# logger100.net
KiCad netlist of a schematic drawn in EAGLE
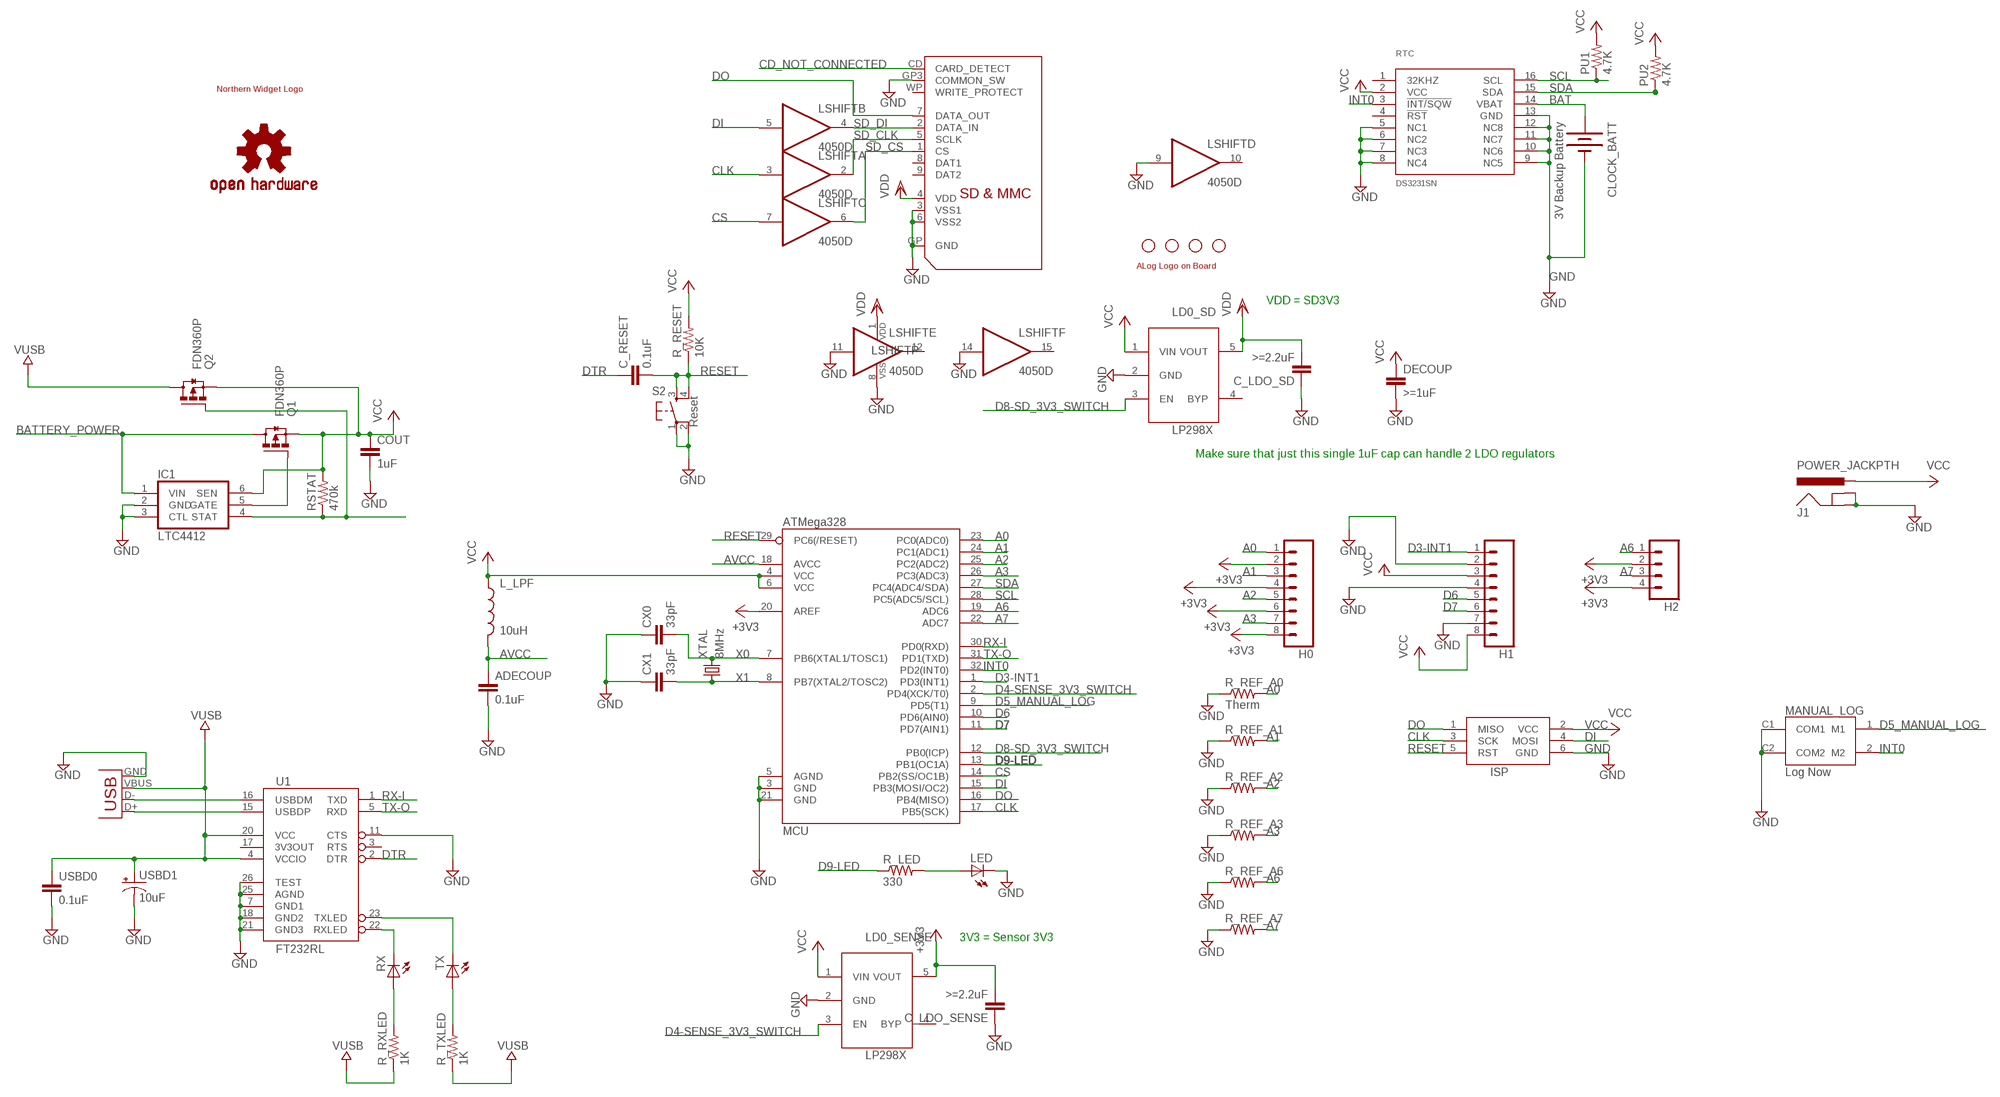
[diagram p0: schematic, sheet 1]

(export (version "E")
  (design (tool "Eeschema 10.0.6"))
  (components
    (comp (ref "ADECOUP")
      (value "0.1uF")
      (footprint "eagle-import:C0603")
      (libsource (lib "eagle-import") (part "resistor_C-EUC0603"))
    )
    (comp (ref "CLOCK_BATT")
      (value "3V Backup Battery")
      (footprint "eagle-import:BATTCON_12MM_PTH")
      (libsource (lib "eagle-import") (part "BATTERY12PTH"))
    )
    (comp (ref "COUT")
      (value "1uF")
      (footprint "eagle-import:C0603-ROUND")
      (libsource (lib "eagle-import") (part "C-EUC0603"))
    )
    (comp (ref "CX0")
      (value "33pF")
      (footprint "eagle-import:C0603")
      (libsource (lib "eagle-import") (part "resistor_C-EUC0603"))
    )
    (comp (ref "CX1")
      (value "33pF")
      (footprint "eagle-import:C0603")
      (libsource (lib "eagle-import") (part "resistor_C-EUC0603"))
    )
    (comp (ref "C_LDO_SD")
      (value ">=2.2uF")
      (footprint "eagle-import:C0603")
      (libsource (lib "eagle-import") (part "resistor_C-EUC0603"))
    )
    (comp (ref "C_LDO_SENSE")
      (value ">=2.2uF")
      (footprint "eagle-import:C0603")
      (libsource (lib "eagle-import") (part "resistor_C-EUC0603"))
    )
    (comp (ref "C_RESET")
      (value "0.1uF")
      (footprint "eagle-import:C0603")
      (libsource (lib "eagle-import") (part "resistor_C-EUC0603"))
    )
    (comp (ref "DECOUP")
      (value ">=1uF")
      (footprint "eagle-import:C0603")
      (libsource (lib "eagle-import") (part "resistor_C-EUC0603"))
    )
    (comp (ref "H0")
      (value "M083.5MM-8")
      (footprint "eagle-import:SCREWTERMINAL-3.5MM-8")
      (libsource (lib "eagle-import") (part "M083.5MM-8"))
    )
    (comp (ref "H1")
      (value "M083.5MM-8")
      (footprint "eagle-import:SCREWTERMINAL-3.5MM-8")
      (libsource (lib "eagle-import") (part "M083.5MM-8"))
    )
    (comp (ref "H2")
      (value "M04SCREW")
      (footprint "eagle-import:SCREWTERMINAL-3.5MM-4")
      (libsource (lib "eagle-import") (part "M04SCREW"))
    )
    (comp (ref "IC1")
      (value "LTC4412")
      (footprint "eagle-import:TSOT23-6")
      (libsource (lib "eagle-import") (part "LTC4412S6E"))
    )
    (comp (ref "ISP")
      (value "AVRISP-6")
      (footprint "eagle-import:AVRISP")
      (libsource (lib "eagle-import") (part "AVRISP-6"))
    )
    (comp (ref "J1")
      (value "POWER_JACKPTH")
      (footprint "eagle-import:POWER_JACK_PTH")
      (libsource (lib "eagle-import") (part "POWER_JACKPTH"))
    )
    (comp (ref "JP1")
      (value "STAND-OFF")
      (footprint "eagle-import:STAND-OFF")
      (libsource (lib "eagle-import") (part "STAND-OFF"))
    )
    (comp (ref "JP2")
      (value "STAND-OFF")
      (footprint "eagle-import:STAND-OFF")
      (libsource (lib "eagle-import") (part "STAND-OFF"))
    )
    (comp (ref "JP3")
      (value "STAND-OFF")
      (footprint "eagle-import:STAND-OFF")
      (libsource (lib "eagle-import") (part "STAND-OFF"))
    )
    (comp (ref "JP4")
      (value "STAND-OFF")
      (footprint "eagle-import:STAND-OFF")
      (libsource (lib "eagle-import") (part "STAND-OFF"))
    )
    (comp (ref "JP5")
      (value "USB-B")
      (footprint "eagle-import:USB-B-PTH")
      (libsource (lib "eagle-import") (part "USBPTH"))
    )
    (comp (ref "LD0_SD")
      (value "LP2985")
      (footprint "eagle-import:SOT23-5L")
      (libsource (lib "eagle-import") (part "LP298XS"))
    )
    (comp (ref "LD0_SENSE")
      (value "LP2985")
      (footprint "eagle-import:SOT23-5L")
      (libsource (lib "eagle-import") (part "LP298XS"))
    )
    (comp (ref "LED")
      (value "LED3MM")
      (footprint "eagle-import:LED3MM")
      (libsource (lib "eagle-import") (part "LED3MM"))
    )
    (comp (ref "LOGO1")
      (value "OSHW-LOGOM")
      (footprint "eagle-import:OSHW-LOGO-M")
      (libsource (lib "eagle-import") (part "OSHW-LOGOM"))
    )
    (comp (ref "LSHIFT")
      (value "4050D")
      (footprint "eagle-import:SO16")
      (libsource (lib "eagle-import") (part "4050D"))
    )
    (comp (ref "L_LPF")
      (value "10uH")
      (footprint "eagle-import:0805")
      (libsource (lib "eagle-import") (part "INDUCTOR0805"))
    )
    (comp (ref "MANUAL_LOG")
      (value "Log Now")
      (footprint "eagle-import:TL_BUTTON")
      (libsource (lib "eagle-import") (part "TL3350'TL3350'"))
    )
    (comp (ref "MCU")
      (value "ATMega328")
      (footprint "eagle-import:TQFP32-08")
      (libsource (lib "eagle-import") (part "ATMEGA168"))
    )
    (comp (ref "PU1")
      (value "4.7K")
      (footprint "eagle-import:R0603")
      (libsource (lib "eagle-import") (part "R-US_R0603"))
    )
    (comp (ref "PU2")
      (value "4.7K")
      (footprint "eagle-import:R0603")
      (libsource (lib "eagle-import") (part "R-US_R0603"))
    )
    (comp (ref "Q1")
      (value "FDN360P")
      (footprint "eagle-import:SUPER-SOT3")
      (libsource (lib "eagle-import") (part "FDN360P"))
    )
    (comp (ref "Q2")
      (value "FDN360P")
      (footprint "eagle-import:SUPER-SOT3")
      (libsource (lib "eagle-import") (part "FDN360P"))
    )
    (comp (ref "RSTAT")
      (value "470k")
      (footprint "eagle-import:R0603")
      (libsource (lib "eagle-import") (part "R-US_R0603"))
    )
    (comp (ref "RTC")
      (value "DS3231SN")
      (footprint "eagle-import:SO16W")
      (libsource (lib "eagle-import") (part "DS3231SN"))
    )
    (comp (ref "RX")
      (value "LED0603")
      (footprint "eagle-import:LED-0603")
      (libsource (lib "eagle-import") (part "SparkFun-LED_LED0603"))
    )
    (comp (ref "R_LED")
      (value "330")
      (footprint "eagle-import:R0603")
      (libsource (lib "eagle-import") (part "R-US_R0603"))
    )
    (comp (ref "R_REF_A0")
      (value "Therm")
      (footprint "eagle-import:0207_10")
      (libsource (lib "eagle-import") (part "resistor_R-US_0207/10"))
    )
    (comp (ref "R_REF_A1")
      (value "R-US_0207/10")
      (footprint "eagle-import:0207_10")
      (libsource (lib "eagle-import") (part "resistor_R-US_0207/10"))
    )
    (comp (ref "R_REF_A2")
      (value "R-US_0207/10")
      (footprint "eagle-import:0207_10")
      (libsource (lib "eagle-import") (part "resistor_R-US_0207/10"))
    )
    (comp (ref "R_REF_A3")
      (value "R-US_0207/10")
      (footprint "eagle-import:0207_10")
      (libsource (lib "eagle-import") (part "resistor_R-US_0207/10"))
    )
    (comp (ref "R_REF_A6")
      (value "R-US_0207/10")
      (footprint "eagle-import:0207_10")
      (libsource (lib "eagle-import") (part "resistor_R-US_0207/10"))
    )
    (comp (ref "R_REF_A7")
      (value "R-US_0207/10")
      (footprint "eagle-import:0207_10")
      (libsource (lib "eagle-import") (part "resistor_R-US_0207/10"))
    )
    (comp (ref "R_RESET")
      (value "10K")
      (footprint "eagle-import:R0603")
      (libsource (lib "eagle-import") (part "R-US_R0603"))
    )
    (comp (ref "R_RXLED")
      (value "1K")
      (footprint "eagle-import:R0603")
      (libsource (lib "eagle-import") (part "R-US_R0603"))
    )
    (comp (ref "R_TXLED")
      (value "1K")
      (footprint "eagle-import:R0603")
      (libsource (lib "eagle-import") (part "R-US_R0603"))
    )
    (comp (ref "S2")
      (value "Reset")
      (footprint "eagle-import:TACTILE_SWITCH_SMD")
      (libsource (lib "eagle-import") (part "TAC_SWITCHSND"))
    )
    (comp (ref "SD")
      (value "SDMMC06132")
      (footprint "eagle-import:06132")
      (libsource (lib "eagle-import") (part "SDMMC06132"))
    )
    (comp (ref "TX")
      (value "LED0603")
      (footprint "eagle-import:LED-0603")
      (libsource (lib "eagle-import") (part "SparkFun-LED_LED0603"))
    )
    (comp (ref "U$1")
      (value "NWLOGO")
      (footprint "eagle-import:NWLOGO")
      (libsource (lib "eagle-import") (part "NWLOGO"))
    )
    (comp (ref "U$2")
      (value "ALOG_LOGO_V1_5.5MM")
      (footprint "eagle-import:ALOG_LOGO_V1_SMALL")
      (libsource (lib "eagle-import") (part "ALOG_LOGO_V1_5.5MM"))
    )
    (comp (ref "U1")
      (value "FT232RL")
      (footprint "eagle-import:SSOP28DB")
      (libsource (lib "eagle-import") (part "FT232RL-BASICSSOP"))
    )
    (comp (ref "USBD0")
      (value "0.1uF")
      (footprint "eagle-import:C0603")
      (libsource (lib "eagle-import") (part "resistor_C-EUC0603"))
    )
    (comp (ref "USBD1")
      (value "10uF")
      (footprint "eagle-import:EIA3216")
      (libsource (lib "eagle-import") (part "CAP_POL1206"))
    )
    (comp (ref "XTAL")
      (value "8MHz")
      (footprint "eagle-import:HC49U-V")
      (libsource (lib "eagle-import") (part "CRYSTALHC49UV"))
    )
  )
  (nets
    (net (code "1") (name "+3V3") (class "Default")
      (node (ref "C_LDO_SENSE") (pin "2") (pinfunction "2_2") (pintype "passive"))
      (node (ref "H0") (pin "2") (pinfunction "2_2") (pintype "passive"))
      (node (ref "H0") (pin "4") (pinfunction "4_4") (pintype "passive"))
      (node (ref "H0") (pin "6") (pinfunction "6_6") (pintype "passive"))
      (node (ref "H0") (pin "8") (pinfunction "8_8") (pintype "passive"))
      (node (ref "H2") (pin "2") (pinfunction "2_2") (pintype "passive"))
      (node (ref "H2") (pin "4") (pinfunction "4_4") (pintype "passive"))
      (node (ref "LD0_SENSE") (pin "5") (pinfunction "VOUT_5") (pintype "bidirectional"))
      (node (ref "MCU") (pin "20") (pinfunction "AREF_20") (pintype "bidirectional"))
    )
    (net (code "2") (name "/A0") (class "Default")
      (node (ref "H0") (pin "1") (pinfunction "1_1") (pintype "passive"))
      (node (ref "MCU") (pin "23") (pinfunction "PC0(ADC0)_23") (pintype "bidirectional"))
      (node (ref "R_REF_A0") (pin "2") (pinfunction "2_2") (pintype "passive"))
    )
    (net (code "3") (name "/A1") (class "Default")
      (node (ref "H0") (pin "3") (pinfunction "3_3") (pintype "passive"))
      (node (ref "MCU") (pin "24") (pinfunction "PC1(ADC1)_24") (pintype "bidirectional"))
      (node (ref "R_REF_A1") (pin "2") (pinfunction "2_2") (pintype "passive"))
    )
    (net (code "4") (name "/A2") (class "Default")
      (node (ref "H0") (pin "5") (pinfunction "5_5") (pintype "passive"))
      (node (ref "MCU") (pin "25") (pinfunction "PC2(ADC2)_25") (pintype "bidirectional"))
      (node (ref "R_REF_A2") (pin "2") (pinfunction "2_2") (pintype "passive"))
    )
    (net (code "5") (name "/A3") (class "Default")
      (node (ref "H0") (pin "7") (pinfunction "7_7") (pintype "passive"))
      (node (ref "MCU") (pin "26") (pinfunction "PC3(ADC3)_26") (pintype "bidirectional"))
      (node (ref "R_REF_A3") (pin "2") (pinfunction "2_2") (pintype "passive"))
    )
    (net (code "6") (name "/A6") (class "Default")
      (node (ref "H2") (pin "1") (pinfunction "1_1") (pintype "passive"))
      (node (ref "MCU") (pin "19") (pinfunction "ADC6_19") (pintype "bidirectional"))
      (node (ref "R_REF_A6") (pin "2") (pinfunction "2_2") (pintype "passive"))
    )
    (net (code "7") (name "/A7") (class "Default")
      (node (ref "H2") (pin "3") (pinfunction "3_3") (pintype "passive"))
      (node (ref "MCU") (pin "22") (pinfunction "ADC7_22") (pintype "bidirectional"))
      (node (ref "R_REF_A7") (pin "2") (pinfunction "2_2") (pintype "passive"))
    )
    (net (code "8") (name "/AVCC") (class "Default")
      (node (ref "ADECOUP") (pin "1") (pinfunction "1_1") (pintype "passive"))
      (node (ref "L_LPF") (pin "2") (pinfunction "2_2") (pintype "passive"))
      (node (ref "MCU") (pin "18") (pinfunction "AVCC_18") (pintype "bidirectional"))
    )
    (net (code "9") (name "/BAT") (class "Default")
      (node (ref "CLOCK_BATT") (pin "VCC@1") (pinfunction "+_VCC@1") (pintype "power_in"))
      (node (ref "RTC") (pin "14") (pinfunction "VBAT_14") (pintype "bidirectional"))
    )
    (net (code "10") (name "/BATTERY_POWER") (class "Default")
      (node (ref "IC1") (pin "1") (pinfunction "VIN_1") (pintype "input"))
      (node (ref "Q1") (pin "3") (pinfunction "D_3") (pintype "passive"))
    )
    (net (code "11") (name "/CD_NOT_CONNECTED") (class "Default")
      (node (ref "SD") (pin "CD") (pinfunction "CARD_DETECT_CD") (pintype "passive"))
    )
    (net (code "12") (name "/CLK") (class "Default")
      (node (ref "ISP") (pin "3") (pinfunction "SCK_3") (pintype "output"))
      (node (ref "LSHIFT") (pin "3") (pinfunction "I_3") (pintype "input"))
      (node (ref "MCU") (pin "17") (pinfunction "PB5(SCK)_17") (pintype "bidirectional"))
    )
    (net (code "13") (name "/CS") (class "Default")
      (node (ref "LSHIFT") (pin "7") (pinfunction "I_7") (pintype "input"))
      (node (ref "MCU") (pin "14") (pinfunction "PB2(SS/OC1B)_14") (pintype "bidirectional"))
    )
    (net (code "14") (name "/D3-INT1") (class "Default")
      (node (ref "H1") (pin "1") (pinfunction "1_1") (pintype "passive"))
      (node (ref "MCU") (pin "1") (pinfunction "PD3(INT1)_1") (pintype "bidirectional"))
    )
    (net (code "15") (name "/D4-SENSE_3V3_SWITCH") (class "Default")
      (node (ref "LD0_SENSE") (pin "3") (pinfunction "EN_3") (pintype "bidirectional"))
      (node (ref "MCU") (pin "2") (pinfunction "PD4(XCK/T0)_2") (pintype "bidirectional"))
    )
    (net (code "16") (name "/D5_MANUAL_LOG") (class "Default")
      (node (ref "MANUAL_LOG") (pin "1") (pinfunction "M1_1") (pintype "bidirectional"))
      (node (ref "MCU") (pin "9") (pinfunction "PD5(T1)_9") (pintype "bidirectional"))
    )
    (net (code "17") (name "/D6") (class "Default")
      (node (ref "H1") (pin "5") (pinfunction "5_5") (pintype "passive"))
      (node (ref "MCU") (pin "10") (pinfunction "PD6(AIN0)_10") (pintype "bidirectional"))
    )
    (net (code "18") (name "/D7") (class "Default")
      (node (ref "H1") (pin "6") (pinfunction "6_6") (pintype "passive"))
      (node (ref "MCU") (pin "11") (pinfunction "PD7(AIN1)_11") (pintype "bidirectional"))
    )
    (net (code "19") (name "/D8-SD_3V3_SWITCH") (class "Default")
      (node (ref "LD0_SD") (pin "3") (pinfunction "EN_3") (pintype "bidirectional"))
      (node (ref "MCU") (pin "12") (pinfunction "PB0(ICP)_12") (pintype "bidirectional"))
    )
    (net (code "20") (name "/D9-LED") (class "Default")
      (node (ref "MCU") (pin "13") (pinfunction "PB1(OC1A)_13") (pintype "bidirectional"))
      (node (ref "R_LED") (pin "1") (pinfunction "1_1") (pintype "passive"))
    )
    (net (code "21") (name "/DI") (class "Default")
      (node (ref "ISP") (pin "4") (pinfunction "MOSI_4") (pintype "output"))
      (node (ref "LSHIFT") (pin "5") (pinfunction "I_5") (pintype "input"))
      (node (ref "MCU") (pin "15") (pinfunction "PB3(MOSI/OC2)_15") (pintype "bidirectional"))
    )
    (net (code "22") (name "/DO") (class "Default")
      (node (ref "ISP") (pin "1") (pinfunction "MISO_1") (pintype "input"))
      (node (ref "MCU") (pin "16") (pinfunction "PB4(MISO)_16") (pintype "bidirectional"))
      (node (ref "SD") (pin "7") (pinfunction "DATA_OUT_7") (pintype "output"))
    )
    (net (code "23") (name "/DTR") (class "Default")
      (node (ref "C_RESET") (pin "1") (pinfunction "1_1") (pintype "passive"))
      (node (ref "U1") (pin "2") (pinfunction "DTR_2") (pintype "bidirectional"))
    )
    (net (code "24") (name "/INT0") (class "Default")
      (node (ref "MANUAL_LOG") (pin "2") (pinfunction "M2_2") (pintype "bidirectional"))
      (node (ref "MCU") (pin "32") (pinfunction "PD2(INT0)_32") (pintype "bidirectional"))
      (node (ref "RTC") (pin "3") (pinfunction "~{INT/SQW}_3") (pintype "bidirectional"))
    )
    (net (code "25") (name "/RESET") (class "Default")
      (node (ref "C_RESET") (pin "2") (pinfunction "2_2") (pintype "passive"))
      (node (ref "ISP") (pin "5") (pinfunction "RST_5") (pintype "output"))
      (node (ref "MCU") (pin "29") (pinfunction "PC6(/RESET)_29") (pintype "bidirectional"))
      (node (ref "R_RESET") (pin "1") (pinfunction "1_1") (pintype "passive"))
      (node (ref "S2") (pin "3") (pinfunction "3_3") (pintype "passive"))
      (node (ref "S2") (pin "4") (pinfunction "4_4") (pintype "passive"))
    )
    (net (code "26") (name "/RX-I") (class "Default")
      (node (ref "MCU") (pin "30") (pinfunction "PD0(RXD)_30") (pintype "bidirectional"))
      (node (ref "U1") (pin "1") (pinfunction "TXD_1") (pintype "output"))
    )
    (net (code "27") (name "/SCL") (class "Default")
      (node (ref "MCU") (pin "28") (pinfunction "PC5(ADC5/SCL)_28") (pintype "bidirectional"))
      (node (ref "PU1") (pin "1") (pinfunction "1_1") (pintype "passive"))
      (node (ref "RTC") (pin "16") (pinfunction "SCL_16") (pintype "bidirectional"))
    )
    (net (code "28") (name "/SDA") (class "Default")
      (node (ref "MCU") (pin "27") (pinfunction "PC4(ADC4/SDA)_27") (pintype "bidirectional"))
      (node (ref "PU2") (pin "1") (pinfunction "1_1") (pintype "passive"))
      (node (ref "RTC") (pin "15") (pinfunction "SDA_15") (pintype "bidirectional"))
    )
    (net (code "29") (name "/SD_CLK") (class "Default")
      (node (ref "LSHIFT") (pin "2") (pinfunction "O_2") (pintype "output"))
      (node (ref "SD") (pin "5") (pinfunction "SCLK_5") (pintype "input"))
    )
    (net (code "30") (name "/SD_CS") (class "Default")
      (node (ref "LSHIFT") (pin "6") (pinfunction "O_6") (pintype "output"))
      (node (ref "SD") (pin "1") (pinfunction "CS_1") (pintype "input"))
    )
    (net (code "31") (name "/SD_DI") (class "Default")
      (node (ref "LSHIFT") (pin "4") (pinfunction "O_4") (pintype "output"))
      (node (ref "SD") (pin "2") (pinfunction "DATA_IN_2") (pintype "input"))
    )
    (net (code "32") (name "/TX-O") (class "Default")
      (node (ref "MCU") (pin "31") (pinfunction "PD1(TXD)_31") (pintype "bidirectional"))
      (node (ref "U1") (pin "5") (pinfunction "RXD_5") (pintype "input"))
    )
    (net (code "33") (name "/X0") (class "Default")
      (node (ref "CX0") (pin "2") (pinfunction "2_2") (pintype "passive"))
      (node (ref "MCU") (pin "7") (pinfunction "PB6(XTAL1/TOSC1)_7") (pintype "bidirectional"))
      (node (ref "XTAL") (pin "2") (pinfunction "2_2") (pintype "passive"))
    )
    (net (code "34") (name "/X1") (class "Default")
      (node (ref "CX1") (pin "2") (pinfunction "2_2") (pintype "passive"))
      (node (ref "MCU") (pin "8") (pinfunction "PB7(XTAL2/TOSC2)_8") (pintype "bidirectional"))
      (node (ref "XTAL") (pin "1") (pinfunction "1_1") (pintype "passive"))
    )
    (net (code "35") (name "GND") (class "Default")
      (node (ref "ADECOUP") (pin "2") (pinfunction "2_2") (pintype "passive"))
      (node (ref "CLOCK_BATT") (pin "GND") (pinfunction "-_GND") (pintype "power_in"))
      (node (ref "COUT") (pin "2") (pinfunction "2_2") (pintype "passive"))
      (node (ref "CX0") (pin "1") (pinfunction "1_1") (pintype "passive"))
      (node (ref "CX1") (pin "1") (pinfunction "1_1") (pintype "passive"))
      (node (ref "C_LDO_SD") (pin "1") (pinfunction "1_1") (pintype "passive"))
      (node (ref "C_LDO_SENSE") (pin "1") (pinfunction "1_1") (pintype "passive"))
      (node (ref "DECOUP") (pin "2") (pinfunction "2_2") (pintype "passive"))
      (node (ref "H1") (pin "2") (pinfunction "2_2") (pintype "passive"))
      (node (ref "H1") (pin "4") (pinfunction "4_4") (pintype "passive"))
      (node (ref "H1") (pin "7") (pinfunction "7_7") (pintype "passive"))
      (node (ref "IC1") (pin "2") (pinfunction "GND_2") (pintype "passive"))
      (node (ref "IC1") (pin "3") (pinfunction "CTL_3") (pintype "input"))
      (node (ref "ISP") (pin "6") (pinfunction "GND_6") (pintype "power_in"))
      (node (ref "J1") (pin "GND") (pinfunction "GND_GND") (pintype "bidirectional"))
      (node (ref "J1") (pin "GNDBREAK") (pinfunction "GNDBREAK_GNDBREAK") (pintype "bidirectional"))
      (node (ref "JP5") (pin "GND") (pinfunction "GND_GND") (pintype "bidirectional"))
      (node (ref "LD0_SD") (pin "2") (pinfunction "GND_2") (pintype "bidirectional"))
      (node (ref "LD0_SENSE") (pin "2") (pinfunction "GND_2") (pintype "bidirectional"))
      (node (ref "LED") (pin "K") (pinfunction "C_K") (pintype "passive"))
      (node (ref "LSHIFT") (pin "11") (pinfunction "I_11") (pintype "input"))
      (node (ref "LSHIFT") (pin "14") (pinfunction "I_14") (pintype "input"))
      (node (ref "LSHIFT") (pin "8") (pinfunction "VSS_8") (pintype "power_in"))
      (node (ref "LSHIFT") (pin "9") (pinfunction "I_9") (pintype "input"))
      (node (ref "MANUAL_LOG") (pin "C1") (pinfunction "COM1_C1") (pintype "bidirectional"))
      (node (ref "MANUAL_LOG") (pin "C2") (pinfunction "COM2_C2") (pintype "bidirectional"))
      (node (ref "MCU") (pin "21") (pinfunction "GND_21") (pintype "bidirectional"))
      (node (ref "MCU") (pin "3") (pinfunction "GND_3") (pintype "bidirectional"))
      (node (ref "MCU") (pin "5") (pinfunction "AGND_5") (pintype "bidirectional"))
      (node (ref "RTC") (pin "10") (pinfunction "NC6_10") (pintype "bidirectional"))
      (node (ref "RTC") (pin "11") (pinfunction "NC7_11") (pintype "bidirectional"))
      (node (ref "RTC") (pin "12") (pinfunction "NC8_12") (pintype "bidirectional"))
      (node (ref "RTC") (pin "13") (pinfunction "GND_13") (pintype "bidirectional"))
      (node (ref "RTC") (pin "5") (pinfunction "NC1_5") (pintype "bidirectional"))
      (node (ref "RTC") (pin "6") (pinfunction "NC2_6") (pintype "bidirectional"))
      (node (ref "RTC") (pin "7") (pinfunction "NC3_7") (pintype "bidirectional"))
      (node (ref "RTC") (pin "8") (pinfunction "NC4_8") (pintype "bidirectional"))
      (node (ref "RTC") (pin "9") (pinfunction "NC5_9") (pintype "bidirectional"))
      (node (ref "R_REF_A0") (pin "1") (pinfunction "1_1") (pintype "passive"))
      (node (ref "R_REF_A1") (pin "1") (pinfunction "1_1") (pintype "passive"))
      (node (ref "R_REF_A2") (pin "1") (pinfunction "1_1") (pintype "passive"))
      (node (ref "R_REF_A3") (pin "1") (pinfunction "1_1") (pintype "passive"))
      (node (ref "R_REF_A6") (pin "1") (pinfunction "1_1") (pintype "passive"))
      (node (ref "R_REF_A7") (pin "1") (pinfunction "1_1") (pintype "passive"))
      (node (ref "S2") (pin "1") (pinfunction "1_1") (pintype "passive"))
      (node (ref "S2") (pin "2") (pinfunction "2_2") (pintype "passive"))
      (node (ref "SD") (pin "3") (pinfunction "VSS1_3") (pintype "power_in"))
      (node (ref "SD") (pin "6") (pinfunction "VSS2_6") (pintype "power_in"))
      (node (ref "SD") (pin "GP") (pinfunction "GND_GP") (pintype "power_in"))
      (node (ref "SD") (pin "GP3") (pinfunction "COMMON_SW_GP3") (pintype "passive"))
      (node (ref "U1") (pin "11") (pinfunction "CTS_11") (pintype "bidirectional"))
      (node (ref "U1") (pin "18") (pinfunction "GND2_18") (pintype "power_in"))
      (node (ref "U1") (pin "21") (pinfunction "GND3_21") (pintype "power_in"))
      (node (ref "U1") (pin "25") (pinfunction "AGND_25") (pintype "power_in"))
      (node (ref "U1") (pin "26") (pinfunction "TEST_26") (pintype "input"))
      (node (ref "U1") (pin "7") (pinfunction "GND1_7") (pintype "power_in"))
      (node (ref "USBD0") (pin "2") (pinfunction "2_2") (pintype "passive"))
      (node (ref "USBD1") (pin "C") (pinfunction "-_C") (pintype "passive"))
    )
    (net (code "36") (name "Net-(IC1-GATE)") (class "Default")
      (node (ref "IC1") (pin "5") (pinfunction "GATE_5") (pintype "output"))
      (node (ref "Q1") (pin "1") (pinfunction "G_1") (pintype "passive"))
    )
    (net (code "37") (name "Net-(IC1-STAT)") (class "Default")
      (node (ref "IC1") (pin "4") (pinfunction "STAT_4") (pintype "open_collector"))
      (node (ref "Q2") (pin "1") (pinfunction "G_1") (pintype "passive"))
      (node (ref "RSTAT") (pin "1") (pinfunction "1_1") (pintype "passive"))
    )
    (net (code "38") (name "Net-(LED-PadA)") (class "Default")
      (node (ref "LED") (pin "A") (pinfunction "A_A") (pintype "passive"))
      (node (ref "R_LED") (pin "2") (pinfunction "2_2") (pintype "passive"))
    )
    (net (code "39") (name "Net-(RX-PadA)") (class "Default")
      (node (ref "RX") (pin "A") (pinfunction "A_A") (pintype "passive"))
      (node (ref "R_RXLED") (pin "2") (pinfunction "2_2") (pintype "passive"))
    )
    (net (code "40") (name "Net-(R_TXLED-Pad2)") (class "Default")
      (node (ref "R_TXLED") (pin "2") (pinfunction "2_2") (pintype "passive"))
      (node (ref "TX") (pin "A") (pinfunction "A_A") (pintype "passive"))
    )
    (net (code "41") (name "Net-(U1-RXLED)") (class "Default")
      (node (ref "RX") (pin "C") (pinfunction "C_C") (pintype "passive"))
      (node (ref "U1") (pin "22") (pinfunction "RXLED_22") (pintype "bidirectional"))
    )
    (net (code "42") (name "Net-(U1-TXLED)") (class "Default")
      (node (ref "TX") (pin "C") (pinfunction "C_C") (pintype "passive"))
      (node (ref "U1") (pin "23") (pinfunction "TXLED_23") (pintype "bidirectional"))
    )
    (net (code "43") (name "Net-(U1-USBDM)") (class "Default")
      (node (ref "JP5") (pin "D-") (pinfunction "D-_D-") (pintype "bidirectional"))
      (node (ref "U1") (pin "16") (pinfunction "USBDM_16") (pintype "bidirectional"))
    )
    (net (code "44") (name "Net-(U1-USBDP)") (class "Default")
      (node (ref "JP5") (pin "D+") (pinfunction "D+_D+") (pintype "bidirectional"))
      (node (ref "U1") (pin "15") (pinfunction "USBDP_15") (pintype "bidirectional"))
    )
    (net (code "45") (name "VCC") (class "Default")
      (node (ref "COUT") (pin "1") (pinfunction "1_1") (pintype "passive"))
      (node (ref "DECOUP") (pin "1") (pinfunction "1_1") (pintype "passive"))
      (node (ref "H1") (pin "3") (pinfunction "3_3") (pintype "passive"))
      (node (ref "H1") (pin "8") (pinfunction "8_8") (pintype "passive"))
      (node (ref "IC1") (pin "6") (pinfunction "SEN_6") (pintype "input"))
      (node (ref "ISP") (pin "2") (pinfunction "VCC_2") (pintype "power_in"))
      (node (ref "J1") (pin "PWR") (pinfunction "PWR_PWR") (pintype "bidirectional"))
      (node (ref "LD0_SD") (pin "1") (pinfunction "VIN_1") (pintype "bidirectional"))
      (node (ref "LD0_SENSE") (pin "1") (pinfunction "VIN_1") (pintype "bidirectional"))
      (node (ref "L_LPF") (pin "1") (pinfunction "1_1") (pintype "passive"))
      (node (ref "MCU") (pin "4") (pinfunction "VCC_4") (pintype "bidirectional"))
      (node (ref "MCU") (pin "6") (pinfunction "VCC_6") (pintype "bidirectional"))
      (node (ref "PU1") (pin "2") (pinfunction "2_2") (pintype "passive"))
      (node (ref "PU2") (pin "2") (pinfunction "2_2") (pintype "passive"))
      (node (ref "Q1") (pin "2") (pinfunction "S_2") (pintype "passive"))
      (node (ref "Q2") (pin "2") (pinfunction "S_2") (pintype "passive"))
      (node (ref "RSTAT") (pin "2") (pinfunction "2_2") (pintype "passive"))
      (node (ref "RTC") (pin "2") (pinfunction "VCC_2") (pintype "bidirectional"))
      (node (ref "R_RESET") (pin "2") (pinfunction "2_2") (pintype "passive"))
    )
    (net (code "46") (name "VDD") (class "Default")
      (node (ref "C_LDO_SD") (pin "2") (pinfunction "2_2") (pintype "passive"))
      (node (ref "LD0_SD") (pin "5") (pinfunction "VOUT_5") (pintype "bidirectional"))
      (node (ref "LSHIFT") (pin "1") (pinfunction "VDD_1") (pintype "power_in"))
      (node (ref "SD") (pin "4") (pinfunction "VDD_4") (pintype "power_in"))
    )
    (net (code "47") (name "VUSB") (class "Default")
      (node (ref "JP5") (pin "VBUS") (pinfunction "VBUS_VBUS") (pintype "bidirectional"))
      (node (ref "Q2") (pin "3") (pinfunction "D_3") (pintype "passive"))
      (node (ref "R_RXLED") (pin "1") (pinfunction "1_1") (pintype "passive"))
      (node (ref "R_TXLED") (pin "1") (pinfunction "1_1") (pintype "passive"))
      (node (ref "U1") (pin "20") (pinfunction "VCC_20") (pintype "power_in"))
      (node (ref "U1") (pin "4") (pinfunction "VCCIO_4") (pintype "power_in"))
      (node (ref "USBD0") (pin "1") (pinfunction "1_1") (pintype "passive"))
      (node (ref "USBD1") (pin "A") (pinfunction "+_A") (pintype "passive"))
    )
    (net (code "48") (name "unconnected-(LD0_SD-BYP-Pad4)") (class "Default")
      (node (ref "LD0_SD") (pin "4") (pinfunction "BYP_4") (pintype "bidirectional"))
    )
    (net (code "49") (name "unconnected-(LD0_SENSE-BYP-Pad4)") (class "Default")
      (node (ref "LD0_SENSE") (pin "4") (pinfunction "BYP_4") (pintype "bidirectional"))
    )
    (net (code "50") (name "unconnected-(LSHIFTD-O-Pad10)") (class "Default")
      (node (ref "LSHIFT") (pin "10") (pinfunction "O_10") (pintype "output"))
    )
    (net (code "51") (name "unconnected-(LSHIFTE-O-Pad12)") (class "Default")
      (node (ref "LSHIFT") (pin "12") (pinfunction "O_12") (pintype "output"))
    )
    (net (code "52") (name "unconnected-(LSHIFTF-O-Pad15)") (class "Default")
      (node (ref "LSHIFT") (pin "15") (pinfunction "O_15") (pintype "output"))
    )
    (net (code "53") (name "unconnected-(RTC-32KHZ-Pad1)") (class "Default")
      (node (ref "RTC") (pin "1") (pinfunction "32KHZ_1") (pintype "bidirectional"))
    )
    (net (code "54") (name "unconnected-(RTC-~{RST}-Pad4)") (class "Default")
      (node (ref "RTC") (pin "4") (pinfunction "~{RST}_4") (pintype "bidirectional"))
    )
    (net (code "55") (name "unconnected-(SD-DAT1-Pad8)") (class "Default")
      (node (ref "SD") (pin "8") (pinfunction "DAT1_8") (pintype "bidirectional"))
    )
    (net (code "56") (name "unconnected-(SD-DAT2-Pad9)") (class "Default")
      (node (ref "SD") (pin "9") (pinfunction "DAT2_9") (pintype "bidirectional"))
    )
    (net (code "57") (name "unconnected-(SD-WRITE_PROTECT-PadWP)") (class "Default")
      (node (ref "SD") (pin "WP") (pinfunction "WRITE_PROTECT_WP") (pintype "passive"))
    )
    (net (code "58") (name "unconnected-(U1-3V3OUT-Pad17)") (class "Default")
      (node (ref "U1") (pin "17") (pinfunction "3V3OUT_17") (pintype "output"))
    )
    (net (code "59") (name "unconnected-(U1-RTS-Pad3)") (class "Default")
      (node (ref "U1") (pin "3") (pinfunction "RTS_3") (pintype "bidirectional"))
    )
  )
)
